# 2_interface.net
KiCad netlist of a schematic drawn in Altium Designer
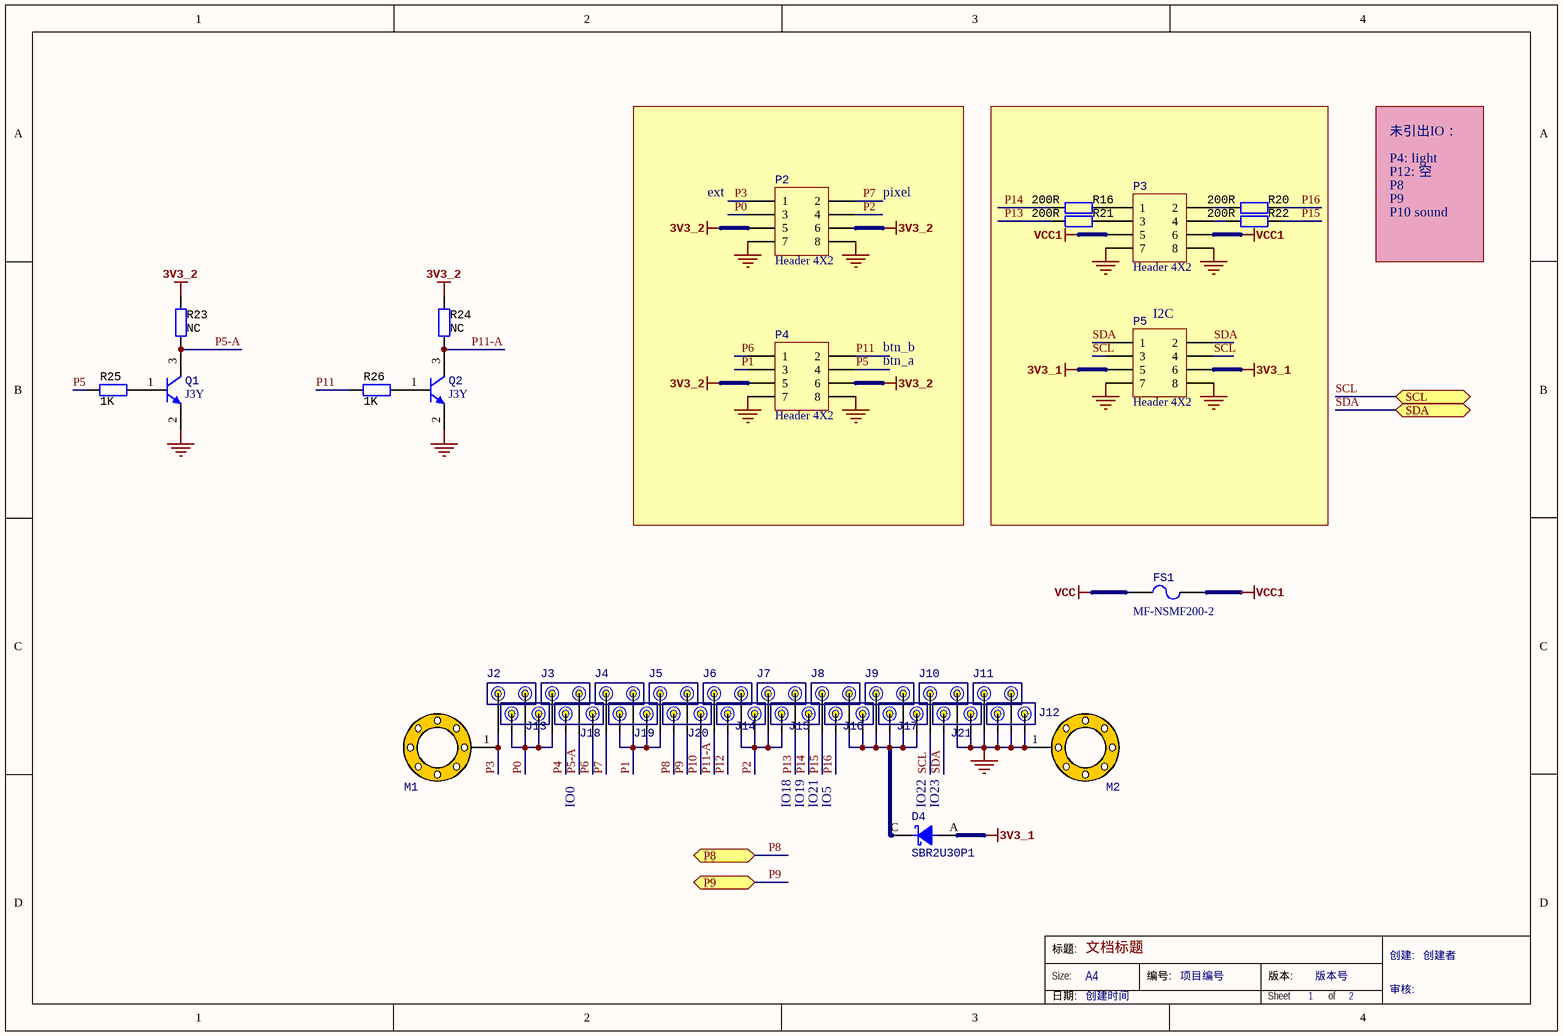
[diagram p0: 2.interface.SchDoc]

(export (version "E")
  (design (tool "Eeschema 10.0.6"))
  (components
    (comp (ref "D4")
      (value "SBR2U30P1")
      (footprint "POWERDI123")
      (fields (field (name "PARTNUMBER") "?") (field (name "PUBLISHER") "Altium Limited"))
      (libsource (lib "03.常用器件") (part "Diode_Schottky"))
    )
    (comp (ref "FS1")
      (value "MF-NSMF200-2")
      (footprint "1206")
      (description "保险管")
      (libsource (lib "Miscellaneous Devices") (part "电子保险丝"))
    )
    (comp (ref "J2") (value "~") (footprint "顶针座子（2.54MM）") (libsource (lib "Schlib1") (part "pogopin")))
    (comp (ref "J3") (value "~") (footprint "顶针座子（2.54MM）") (libsource (lib "Schlib1") (part "pogopin")))
    (comp (ref "J4") (value "~") (footprint "顶针座子（2.54MM）") (libsource (lib "Schlib1") (part "pogopin")))
    (comp (ref "J5") (value "~") (footprint "顶针座子（2.54MM）") (libsource (lib "Schlib1") (part "pogopin")))
    (comp (ref "J6") (value "~") (footprint "顶针座子（2.54MM）") (libsource (lib "Schlib1") (part "pogopin")))
    (comp (ref "J7") (value "~") (footprint "顶针座子（2.54MM）") (libsource (lib "Schlib1") (part "pogopin")))
    (comp (ref "J8") (value "~") (footprint "顶针座子（2.54MM）") (libsource (lib "Schlib1") (part "pogopin")))
    (comp (ref "J9") (value "~") (footprint "顶针座子（2.54MM）") (libsource (lib "Schlib1") (part "pogopin")))
    (comp (ref "J10") (value "~") (footprint "顶针座子（2.54MM）") (libsource (lib "Schlib1") (part "pogopin")))
    (comp (ref "J11") (value "~") (footprint "顶针座子（2.54MM）") (libsource (lib "Schlib1") (part "pogopin")))
    (comp (ref "J12") (value "~") (footprint "顶针座子（2.54MM）") (libsource (lib "Schlib1") (part "pogopin_32")))
    (comp (ref "J13") (value "~") (footprint "顶针座子（2.54MM）") (libsource (lib "Schlib1") (part "pogopin_32")))
    (comp (ref "J14") (value "~") (footprint "顶针座子（2.54MM）") (libsource (lib "Schlib1") (part "pogopin_32")))
    (comp (ref "J15") (value "~") (footprint "顶针座子（2.54MM）") (libsource (lib "Schlib1") (part "pogopin_32")))
    (comp (ref "J16") (value "~") (footprint "顶针座子（2.54MM）") (libsource (lib "Schlib1") (part "pogopin_32")))
    (comp (ref "J17") (value "~") (footprint "顶针座子（2.54MM）") (libsource (lib "Schlib1") (part "pogopin_32")))
    (comp (ref "J18") (value "~") (footprint "顶针座子（2.54MM）") (libsource (lib "Schlib1") (part "pogopin_32")))
    (comp (ref "J19") (value "~") (footprint "顶针座子（2.54MM）") (libsource (lib "Schlib1") (part "pogopin_32")))
    (comp (ref "J20") (value "~") (footprint "顶针座子（2.54MM）") (libsource (lib "Schlib1") (part "pogopin_32")))
    (comp (ref "J21") (value "~") (footprint "顶针座子（2.54MM）") (libsource (lib "Schlib1") (part "pogopin_32")))
    (comp (ref "M1") (value "~") (footprint "3MM螺丝孔") (libsource (lib "labplus-connector") (part "screw")))
    (comp (ref "M2") (value "~") (footprint "3MM螺丝孔") (libsource (lib "labplus-connector") (part "screw")))
    (comp (ref "P2")
      (value "Header 4X2")
      (footprint "HDR2X4")
      (description "Header, 4-Pin, Dual row")
      (fields (field (name "PUBLISHER") "Altium Limited"))
      (libsource (lib "Miscellaneous Connectors") (part "Header 4X2"))
    )
    (comp (ref "P3")
      (value "Header 4X2")
      (footprint "HDR2X4")
      (description "Header, 4-Pin, Dual row")
      (fields (field (name "PUBLISHER") "Altium Limited"))
      (libsource (lib "Miscellaneous Connectors") (part "Header 4X2"))
    )
    (comp (ref "P4")
      (value "Header 4X2")
      (footprint "HDR2X4")
      (description "Header, 4-Pin, Dual row")
      (fields (field (name "PUBLISHER") "Altium Limited"))
      (libsource (lib "Miscellaneous Connectors") (part "Header 4X2"))
    )
    (comp (ref "P5")
      (value "Header 4X2")
      (footprint "HDR2X4")
      (description "Header, 4-Pin, Dual row")
      (fields (field (name "PUBLISHER") "Altium Limited"))
      (libsource (lib "Miscellaneous Connectors") (part "Header 4X2"))
    )
    (comp (ref "Q1")
      (value "J3Y")
      (footprint "DFN 3L")
      (description "NPN General Purpose Amplifier")
      (fields (field (name "PUBLISHER") "Altium Limited"))
      (libsource (lib "Schlib1") (part "2N3904"))
    )
    (comp (ref "Q2")
      (value "J3Y")
      (footprint "DFN 3L")
      (description "NPN General Purpose Amplifier")
      (fields (field (name "PUBLISHER") "Altium Limited"))
      (libsource (lib "Schlib1") (part "2N3904"))
    )
    (comp (ref "R16")
      (value "200R")
      (footprint "0402")
      (description "RES, 1.0k ohm, 5%, 0.1W, 0603")
      (fields
        (field (name "PARTNUMBER") "RC0603JR-071KL")
        (field (name "MANUFACTURER") "Yageo America")
        (field (name "PUBLISHER") "Texas Instruments")
      )
      (libsource (lib "03.常用器件") (part "RES1"))
    )
    (comp (ref "R20")
      (value "200R")
      (footprint "0402")
      (description "RES, 1.0k ohm, 5%, 0.1W, 0603")
      (fields
        (field (name "PARTNUMBER") "RC0603JR-071KL")
        (field (name "MANUFACTURER") "Yageo America")
        (field (name "PUBLISHER") "Texas Instruments")
      )
      (libsource (lib "03.常用器件") (part "RES1"))
    )
    (comp (ref "R21")
      (value "200R")
      (footprint "0402")
      (description "RES, 1.0k ohm, 5%, 0.1W, 0603")
      (fields
        (field (name "PARTNUMBER") "RC0603JR-071KL")
        (field (name "MANUFACTURER") "Yageo America")
        (field (name "PUBLISHER") "Texas Instruments")
      )
      (libsource (lib "03.常用器件") (part "RES1"))
    )
    (comp (ref "R22")
      (value "200R")
      (footprint "0402")
      (description "RES, 1.0k ohm, 5%, 0.1W, 0603")
      (fields
        (field (name "PARTNUMBER") "RC0603JR-071KL")
        (field (name "MANUFACTURER") "Yageo America")
        (field (name "PUBLISHER") "Texas Instruments")
      )
      (libsource (lib "03.常用器件") (part "RES1"))
    )
    (comp (ref "R23")
      (value "NC")
      (footprint "0402")
      (description "RES, 1.0k ohm, 5%, 0.1W, 0603")
      (fields
        (field (name "PARTNUMBER") "RC0603JR-071KL")
        (field (name "MANUFACTURER") "Yageo America")
        (field (name "PUBLISHER") "Texas Instruments")
      )
      (libsource (lib "") (part "RES1_1"))
    )
    (comp (ref "R24")
      (value "NC")
      (footprint "0402")
      (description "RES, 1.0k ohm, 5%, 0.1W, 0603")
      (fields
        (field (name "PARTNUMBER") "RC0603JR-071KL")
        (field (name "MANUFACTURER") "Yageo America")
        (field (name "PUBLISHER") "Texas Instruments")
      )
      (libsource (lib "") (part "RES1_1"))
    )
    (comp (ref "R25")
      (value "1K")
      (footprint "0402")
      (description "RES, 1.0k ohm, 5%, 0.1W, 0603")
      (fields
        (field (name "PARTNUMBER") "RC0603JR-071KL")
        (field (name "MANUFACTURER") "Yageo America")
        (field (name "PUBLISHER") "Texas Instruments")
      )
      (libsource (lib "") (part "RES1_2"))
    )
    (comp (ref "R26")
      (value "1K")
      (footprint "0402")
      (description "RES, 1.0k ohm, 5%, 0.1W, 0603")
      (fields
        (field (name "PARTNUMBER") "RC0603JR-071KL")
        (field (name "MANUFACTURER") "Yageo America")
        (field (name "PUBLISHER") "Texas Instruments")
      )
      (libsource (lib "") (part "RES1_2"))
    )
  )
  (nets
    (net (code "1") (name "/P0") (class "Default")
      (node (ref "J13") (pin "1") (pinfunction "1_1") (pintype "passive"))
      (node (ref "J13") (pin "2") (pinfunction "2_2") (pintype "passive"))
      (node (ref "J2") (pin "2") (pinfunction "2_2") (pintype "passive"))
      (node (ref "J3") (pin "1") (pinfunction "1_1") (pintype "passive"))
      (node (ref "P2") (pin "3") (pinfunction "3_3") (pintype "passive"))
    )
    (net (code "2") (name "/P1") (class "Default")
      (node (ref "J19") (pin "1") (pinfunction "1_1") (pintype "passive"))
      (node (ref "J19") (pin "2") (pinfunction "2_2") (pintype "passive"))
      (node (ref "J4") (pin "2") (pinfunction "2_2") (pintype "passive"))
      (node (ref "J5") (pin "1") (pinfunction "1_1") (pintype "passive"))
      (node (ref "P4") (pin "3") (pinfunction "3_3") (pintype "passive"))
    )
    (net (code "3") (name "/P2") (class "Default")
      (node (ref "J14") (pin "2") (pinfunction "2_2") (pintype "passive"))
      (node (ref "J15") (pin "1") (pinfunction "1_1") (pintype "passive"))
      (node (ref "J6") (pin "2") (pinfunction "2_2") (pintype "passive"))
      (node (ref "J7") (pin "1") (pinfunction "1_1") (pintype "passive"))
      (node (ref "P2") (pin "4") (pinfunction "4_4") (pintype "passive"))
    )
    (net (code "4") (name "/P3") (class "Default")
      (node (ref "J2") (pin "1") (pinfunction "1_1") (pintype "passive"))
      (node (ref "M1") (pin "1") (pinfunction "1_1") (pintype "passive"))
      (node (ref "P2") (pin "1") (pinfunction "1_1") (pintype "passive"))
    )
    (net (code "5") (name "/P4") (class "Default")
      (node (ref "J18") (pin "1") (pinfunction "1_1") (pintype "passive"))
    )
    (net (code "6") (name "/P5") (class "Default")
      (node (ref "P4") (pin "4") (pinfunction "4_4") (pintype "passive"))
      (node (ref "R25") (pin "1") (pinfunction "1_1") (pintype "passive"))
    )
    (net (code "7") (name "/P5-A") (class "Default")
      (node (ref "J3") (pin "2") (pinfunction "2_2") (pintype "passive"))
      (node (ref "Q1") (pin "3") (pinfunction "C_3") (pintype "passive"))
      (node (ref "R23") (pin "2") (pinfunction "2_2") (pintype "passive"))
    )
    (net (code "8") (name "/P6") (class "Default")
      (node (ref "J18") (pin "2") (pinfunction "2_2") (pintype "passive"))
      (node (ref "P4") (pin "1") (pinfunction "1_1") (pintype "passive"))
    )
    (net (code "9") (name "/P7") (class "Default")
      (node (ref "J4") (pin "1") (pinfunction "1_1") (pintype "passive"))
      (node (ref "P2") (pin "2") (pinfunction "2_2") (pintype "passive"))
    )
    (net (code "10") (name "/P8") (class "Default")
      (node (ref "J20") (pin "1") (pinfunction "1_1") (pintype "passive"))
    )
    (net (code "11") (name "/P9") (class "Default")
      (node (ref "J5") (pin "2") (pinfunction "2_2") (pintype "passive"))
    )
    (net (code "12") (name "/P10") (class "Default")
      (node (ref "J20") (pin "2") (pinfunction "2_2") (pintype "passive"))
    )
    (net (code "13") (name "/P11") (class "Default")
      (node (ref "P4") (pin "2") (pinfunction "2_2") (pintype "passive"))
      (node (ref "R26") (pin "1") (pinfunction "1_1") (pintype "passive"))
    )
    (net (code "14") (name "/P11-A") (class "Default")
      (node (ref "J6") (pin "1") (pinfunction "1_1") (pintype "passive"))
      (node (ref "Q2") (pin "3") (pinfunction "C_3") (pintype "passive"))
      (node (ref "R24") (pin "2") (pinfunction "2_2") (pintype "passive"))
    )
    (net (code "15") (name "/P12") (class "Default")
      (node (ref "J14") (pin "1") (pinfunction "1_1") (pintype "passive"))
    )
    (net (code "16") (name "/P13") (class "Default")
      (node (ref "J7") (pin "2") (pinfunction "2_2") (pintype "passive"))
      (node (ref "R21") (pin "1") (pinfunction "1_1") (pintype "passive"))
    )
    (net (code "17") (name "/P14") (class "Default")
      (node (ref "J15") (pin "2") (pinfunction "2_2") (pintype "passive"))
      (node (ref "R16") (pin "1") (pinfunction "1_1") (pintype "passive"))
    )
    (net (code "18") (name "/P15") (class "Default")
      (node (ref "J8") (pin "1") (pinfunction "1_1") (pintype "passive"))
      (node (ref "R22") (pin "2") (pinfunction "2_2") (pintype "passive"))
    )
    (net (code "19") (name "/P16") (class "Default")
      (node (ref "J16") (pin "1") (pinfunction "1_1") (pintype "passive"))
      (node (ref "R20") (pin "2") (pinfunction "2_2") (pintype "passive"))
    )
    (net (code "20") (name "/SCL") (class "Default")
      (node (ref "J10") (pin "1") (pinfunction "1_1") (pintype "passive"))
      (node (ref "P5") (pin "3") (pinfunction "3_3") (pintype "passive"))
      (node (ref "P5") (pin "4") (pinfunction "4_4") (pintype "passive"))
    )
    (net (code "21") (name "/SDA") (class "Default")
      (node (ref "J21") (pin "1") (pinfunction "1_1") (pintype "passive"))
      (node (ref "P5") (pin "1") (pinfunction "1_1") (pintype "passive"))
      (node (ref "P5") (pin "2") (pinfunction "2_2") (pintype "passive"))
    )
    (net (code "22") (name "3V3_1") (class "Default")
      (node (ref "D4") (pin "A") (pinfunction "ANODE_A") (pintype "passive"))
      (node (ref "P5") (pin "5") (pinfunction "5_5") (pintype "passive"))
      (node (ref "P5") (pin "6") (pinfunction "6_6") (pintype "passive"))
    )
    (net (code "23") (name "3V3_2") (class "Default")
      (node (ref "P2") (pin "5") (pinfunction "5_5") (pintype "passive"))
      (node (ref "P2") (pin "6") (pinfunction "6_6") (pintype "passive"))
      (node (ref "P4") (pin "5") (pinfunction "5_5") (pintype "passive"))
      (node (ref "P4") (pin "6") (pinfunction "6_6") (pintype "passive"))
      (node (ref "R23") (pin "1") (pinfunction "1_1") (pintype "passive"))
      (node (ref "R24") (pin "1") (pinfunction "1_1") (pintype "passive"))
    )
    (net (code "24") (name "<NO NET>") (class "Default")
      (node (ref "J10") (pin "2") (pinfunction "2_2") (pintype "passive"))
      (node (ref "J11") (pin "1") (pinfunction "1_1") (pintype "passive"))
      (node (ref "J11") (pin "2") (pinfunction "2_2") (pintype "passive"))
      (node (ref "J12") (pin "1") (pinfunction "1_1") (pintype "passive"))
      (node (ref "J12") (pin "2") (pinfunction "2_2") (pintype "passive"))
      (node (ref "J21") (pin "2") (pinfunction "2_2") (pintype "passive"))
      (node (ref "M2") (pin "1") (pinfunction "1_1") (pintype "passive"))
      (node (ref "P2") (pin "7") (pinfunction "7_7") (pintype "passive"))
      (node (ref "P2") (pin "8") (pinfunction "8_8") (pintype "passive"))
      (node (ref "P3") (pin "7") (pinfunction "7_7") (pintype "passive"))
      (node (ref "P3") (pin "8") (pinfunction "8_8") (pintype "passive"))
      (node (ref "P4") (pin "7") (pinfunction "7_7") (pintype "passive"))
      (node (ref "P4") (pin "8") (pinfunction "8_8") (pintype "passive"))
      (node (ref "P5") (pin "7") (pinfunction "7_7") (pintype "passive"))
      (node (ref "P5") (pin "8") (pinfunction "8_8") (pintype "passive"))
      (node (ref "Q1") (pin "2") (pinfunction "E_2") (pintype "passive"))
      (node (ref "Q2") (pin "2") (pinfunction "E_2") (pintype "passive"))
    )
    (net (code "25") (name "Net-(D4-CATHODE)") (class "Default")
      (node (ref "D4") (pin "C") (pinfunction "CATHODE_C") (pintype "passive"))
      (node (ref "J16") (pin "2") (pinfunction "2_2") (pintype "passive"))
      (node (ref "J17") (pin "1") (pinfunction "1_1") (pintype "passive"))
      (node (ref "J17") (pin "2") (pinfunction "2_2") (pintype "passive"))
      (node (ref "J8") (pin "2") (pinfunction "2_2") (pintype "passive"))
      (node (ref "J9") (pin "1") (pinfunction "1_1") (pintype "passive"))
      (node (ref "J9") (pin "2") (pinfunction "2_2") (pintype "passive"))
    )
    (net (code "26") (name "Net-(P3-Pad1)") (class "Default")
      (node (ref "P3") (pin "1") (pinfunction "1_1") (pintype "passive"))
      (node (ref "R16") (pin "2") (pinfunction "2_2") (pintype "passive"))
    )
    (net (code "27") (name "Net-(P3-Pad2)") (class "Default")
      (node (ref "P3") (pin "2") (pinfunction "2_2") (pintype "passive"))
      (node (ref "R20") (pin "1") (pinfunction "1_1") (pintype "passive"))
    )
    (net (code "28") (name "Net-(P3-Pad3)") (class "Default")
      (node (ref "P3") (pin "3") (pinfunction "3_3") (pintype "passive"))
      (node (ref "R21") (pin "2") (pinfunction "2_2") (pintype "passive"))
    )
    (net (code "29") (name "Net-(P3-Pad4)") (class "Default")
      (node (ref "P3") (pin "4") (pinfunction "4_4") (pintype "passive"))
      (node (ref "R22") (pin "1") (pinfunction "1_1") (pintype "passive"))
    )
    (net (code "30") (name "Net-(Q1-B)") (class "Default")
      (node (ref "Q1") (pin "1") (pinfunction "B_1") (pintype "passive"))
      (node (ref "R25") (pin "2") (pinfunction "2_2") (pintype "passive"))
    )
    (net (code "31") (name "Net-(Q2-B)") (class "Default")
      (node (ref "Q2") (pin "1") (pinfunction "B_1") (pintype "passive"))
      (node (ref "R26") (pin "2") (pinfunction "2_2") (pintype "passive"))
    )
    (net (code "32") (name "VCC") (class "Default")
      (node (ref "FS1") (pin "2") (pinfunction "1_2") (pintype "passive"))
    )
    (net (code "33") (name "VCC1") (class "Default")
      (node (ref "FS1") (pin "1") (pinfunction "0_1") (pintype "passive"))
      (node (ref "P3") (pin "5") (pinfunction "5_5") (pintype "passive"))
      (node (ref "P3") (pin "6") (pinfunction "6_6") (pintype "passive"))
    )
  )
)
